# powercircuit.net
KiCad netlist of a schematic drawn in Altium Designer
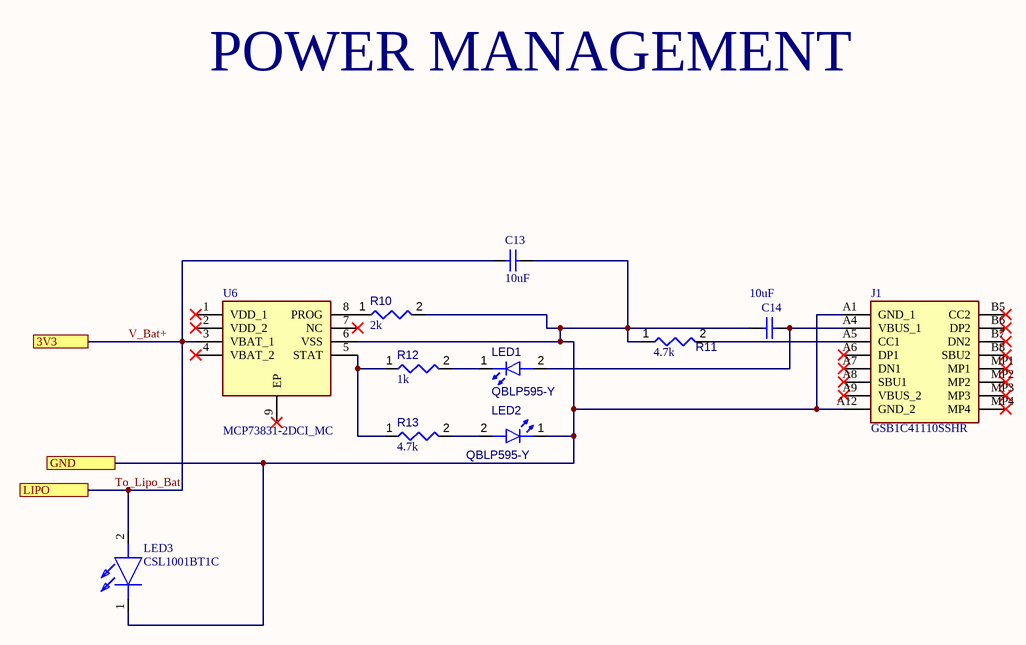
[diagram p0: powercircuit.SchDoc]

(export (version "E")
  (design (tool "Eeschema 10.0.6"))
  (components
    (comp (ref "C13")
      (value "10uF")
      (footprint "CAPC1608X90X35ML10T15")
      (description "Chip Capacitor, 0.1 uF, +/- 10%, 50 V, -55 to 125 degC, 0603 (1608 Metric), RoHS, Tape and Reel")
      (fields (field (name "TOLERANCE") "10%") (field (name "VOLTAGE") "50V"))
      (libsource (lib "Altium Content Vault") (part "CAP-NP-2"))
    )
    (comp (ref "C14")
      (value "10uF")
      (footprint "CAPC1608X90X35ML10T15")
      (description "Chip Capacitor, 0.1 uF, +/- 10%, 50 V, -55 to 125 degC, 0603 (1608 Metric), RoHS, Tape and Reel")
      (fields (field (name "TOLERANCE") "10%") (field (name "VOLTAGE") "50V"))
      (libsource (lib "Altium Content Vault") (part "CAP-NP-2"))
    )
    (comp (ref "J1")
      (value "GSB1C41110SSHR")
      (footprint "PcbLib1:GSB1C41110SSHR")
      (description "Connector")
      (libsource (lib "*") (part "GSB1C41110SSHR"))
    )
    (comp (ref "LED1")
      (value "QBLP595-Y")
      (footprint "QTB-QBLP595_V")
      (description "Chip LED 0402, Yellow, 0.02 A, 3.1 to 3.7 V, -40 to 80 degC, 2-Pin SMD, RoHS, Tape and Reel")
      (libsource (lib "JCGada") (part "LED-KA-2"))
    )
    (comp (ref "LED2")
      (value "QBLP595-Y")
      (footprint "QTB-QBLP595_V")
      (description "Chip LED 0402, Yellow, 0.02 A, 3.1 to 3.7 V, -40 to 80 degC, 2-Pin SMD, RoHS, Tape and Reel")
      (libsource (lib "JCGada") (part "LED-KA-2"))
    )
    (comp (ref "LED3")
      (value "CSL1001BT1C")
      (footprint "PcbLib1:CSL1001BT1C")
      (description "LED")
      (fields (field (name "MOUSER PART NUMBER") "755-CSL1001BT1C"))
      (libsource (lib "*") (part "CSL1001BT1C"))
    )
    (comp (ref "R10")
      (value "2k")
      (footprint "RESC0402(1005)_L")
      (description "2K 0.063W 5% 0402 (1005 Metric)  SMD")
      (fields (field (name "TOLERANCE") "5%") (field (name "POWER") "63mW"))
      (libsource (lib "JCGada") (part "2KR2J"))
    )
    (comp (ref "R11")
      (value "4.7k")
      (footprint "RESC0402(1005)_L")
      (description "Chip Resistor, 4,7 kOhms, +/-1 %, 63 mW, -55 to 155 degC, 0402")
      (fields (field (name "POWER") "63mW") (field (name "TOLERANCE") "1%"))
      (libsource (lib "JCGada") (part "RES-2"))
    )
    (comp (ref "R12")
      (value "1k")
      (footprint "RESC0402(1005)_L")
      (description "1K 0.063W 5% 0402 (1005 Metric)  SMD")
      (fields (field (name "POWER") "63mW") (field (name "TOLERANCE") "5%"))
      (libsource (lib "JCGada") (part "1KR2J"))
    )
    (comp (ref "R13")
      (value "4.7k")
      (footprint "RESC0402(1005)_L")
      (description "Chip Resistor, 4,7 kOhms, +/-1 %, 63 mW, -55 to 155 degC, 0402")
      (fields (field (name "POWER") "63mW") (field (name "TOLERANCE") "1%"))
      (libsource (lib "JCGada") (part "RES-2"))
    )
    (comp (ref "U6")
      (value "MCP73831-2DCI_MC")
      (footprint "PcbLib1:SON50P300X200X100-9N-D")
      (description "Integrated Circuit")
      (fields
        (field (name "MANUFACTURER_PART_NUMBER") "MCP73831-2DCI/MC")
        (field (name "MOUSER PART NUMBER") "579-MCP73831-2DCI/MC")
      )
      (libsource (lib "*") (part "MCP73831-2DCI_MC"))
    )
  )
  (nets
    (net (code "1") (name "/GND") (class "Default")
      (node (ref "C13") (pin "1") (pinfunction "1_1") (pintype "passive"))
      (node (ref "C14") (pin "2") (pinfunction "2_2") (pintype "passive"))
      (node (ref "J1") (pin "A1") (pinfunction "GND_1_A1") (pintype "passive"))
      (node (ref "J1") (pin "A12") (pinfunction "GND_2_A12") (pintype "passive"))
      (node (ref "LED2") (pin "1") (pinfunction "K_1") (pintype "passive"))
      (node (ref "LED3") (pin "1") (pinfunction "K_1") (pintype "passive"))
      (node (ref "R10") (pin "2") (pinfunction "2_2") (pintype "passive"))
      (node (ref "R11") (pin "1") (pinfunction "1_1") (pintype "passive"))
      (node (ref "U6") (pin "6") (pinfunction "VSS_6") (pintype "passive"))
    )
    (net (code "2") (name "/To_Lipo_Bat") (class "Default")
      (node (ref "C13") (pin "2") (pinfunction "2_2") (pintype "passive"))
      (node (ref "LED3") (pin "2") (pinfunction "A_2") (pintype "passive"))
      (node (ref "U6") (pin "3") (pinfunction "VBAT_1_3") (pintype "passive"))
    )
    (net (code "3") (name "Net-(J1-CC1)") (class "Default")
      (node (ref "J1") (pin "A5") (pinfunction "CC1_A5") (pintype "passive"))
      (node (ref "R11") (pin "2") (pinfunction "2_2") (pintype "passive"))
    )
    (net (code "4") (name "Net-(J1-VBUS_1)") (class "Default")
      (node (ref "C14") (pin "1") (pinfunction "1_1") (pintype "passive"))
      (node (ref "J1") (pin "A4") (pinfunction "VBUS_1_A4") (pintype "passive"))
      (node (ref "LED1") (pin "2") (pinfunction "A_2") (pintype "passive"))
    )
    (net (code "5") (name "Net-(LED1-K)") (class "Default")
      (node (ref "LED1") (pin "1") (pinfunction "K_1") (pintype "passive"))
      (node (ref "R12") (pin "2") (pinfunction "2_2") (pintype "passive"))
    )
    (net (code "6") (name "Net-(LED2-A)") (class "Default")
      (node (ref "LED2") (pin "2") (pinfunction "A_2") (pintype "passive"))
      (node (ref "R13") (pin "2") (pinfunction "2_2") (pintype "passive"))
    )
    (net (code "7") (name "Net-(U6-PROG)") (class "Default")
      (node (ref "R10") (pin "1") (pinfunction "1_1") (pintype "passive"))
      (node (ref "U6") (pin "8") (pinfunction "PROG_8") (pintype "passive"))
    )
    (net (code "8") (name "Net-(U6-STAT)") (class "Default")
      (node (ref "R12") (pin "1") (pinfunction "1_1") (pintype "passive"))
      (node (ref "R13") (pin "1") (pinfunction "1_1") (pintype "passive"))
      (node (ref "U6") (pin "5") (pinfunction "STAT_5") (pintype "passive"))
    )
    (net (code "9") (name "unconnected-(J1-CC2-PadB5)") (class "Default")
      (node (ref "J1") (pin "B5") (pinfunction "CC2_B5") (pintype "passive+no_connect"))
    )
    (net (code "10") (name "unconnected-(J1-DN1-PadA7)") (class "Default")
      (node (ref "J1") (pin "A7") (pinfunction "DN1_A7") (pintype "passive+no_connect"))
    )
    (net (code "11") (name "unconnected-(J1-DN2-PadB7)") (class "Default")
      (node (ref "J1") (pin "B7") (pinfunction "DN2_B7") (pintype "passive+no_connect"))
    )
    (net (code "12") (name "unconnected-(J1-DP1-PadA6)") (class "Default")
      (node (ref "J1") (pin "A6") (pinfunction "DP1_A6") (pintype "passive+no_connect"))
    )
    (net (code "13") (name "unconnected-(J1-DP2-PadB6)") (class "Default")
      (node (ref "J1") (pin "B6") (pinfunction "DP2_B6") (pintype "passive+no_connect"))
    )
    (net (code "14") (name "unconnected-(J1-PadMP1)") (class "Default")
      (node (ref "J1") (pin "MP1") (pinfunction "MP1_MP1") (pintype "passive+no_connect"))
    )
    (net (code "15") (name "unconnected-(J1-PadMP2)") (class "Default")
      (node (ref "J1") (pin "MP2") (pinfunction "MP2_MP2") (pintype "passive+no_connect"))
    )
    (net (code "16") (name "unconnected-(J1-PadMP3)") (class "Default")
      (node (ref "J1") (pin "MP3") (pinfunction "MP3_MP3") (pintype "passive+no_connect"))
    )
    (net (code "17") (name "unconnected-(J1-PadMP4)") (class "Default")
      (node (ref "J1") (pin "MP4") (pinfunction "MP4_MP4") (pintype "passive+no_connect"))
    )
    (net (code "18") (name "unconnected-(J1-SBU1-PadA8)") (class "Default")
      (node (ref "J1") (pin "A8") (pinfunction "SBU1_A8") (pintype "passive+no_connect"))
    )
    (net (code "19") (name "unconnected-(J1-SBU2-PadB8)") (class "Default")
      (node (ref "J1") (pin "B8") (pinfunction "SBU2_B8") (pintype "passive+no_connect"))
    )
    (net (code "20") (name "unconnected-(J1-VBUS_2-PadA9)") (class "Default")
      (node (ref "J1") (pin "A9") (pinfunction "VBUS_2_A9") (pintype "passive+no_connect"))
    )
    (net (code "21") (name "unconnected-(U6-EP-Pad9)") (class "Default")
      (node (ref "U6") (pin "9") (pinfunction "EP_9") (pintype "passive+no_connect"))
    )
    (net (code "22") (name "unconnected-(U6-NC-Pad7)") (class "Default")
      (node (ref "U6") (pin "7") (pinfunction "NC_7") (pintype "passive+no_connect"))
    )
    (net (code "23") (name "unconnected-(U6-VBAT_2-Pad4)") (class "Default")
      (node (ref "U6") (pin "4") (pinfunction "VBAT_2_4") (pintype "passive+no_connect"))
    )
    (net (code "24") (name "unconnected-(U6-VDD_1-Pad1)") (class "Default")
      (node (ref "U6") (pin "1") (pinfunction "VDD_1_1") (pintype "passive+no_connect"))
    )
    (net (code "25") (name "unconnected-(U6-VDD_2-Pad2)") (class "Default")
      (node (ref "U6") (pin "2") (pinfunction "VDD_2_2") (pintype "passive+no_connect"))
    )
  )
)
